# MICRO_MODULAR_batt2.net
KiCad netlist of a schematic drawn in EAGLE
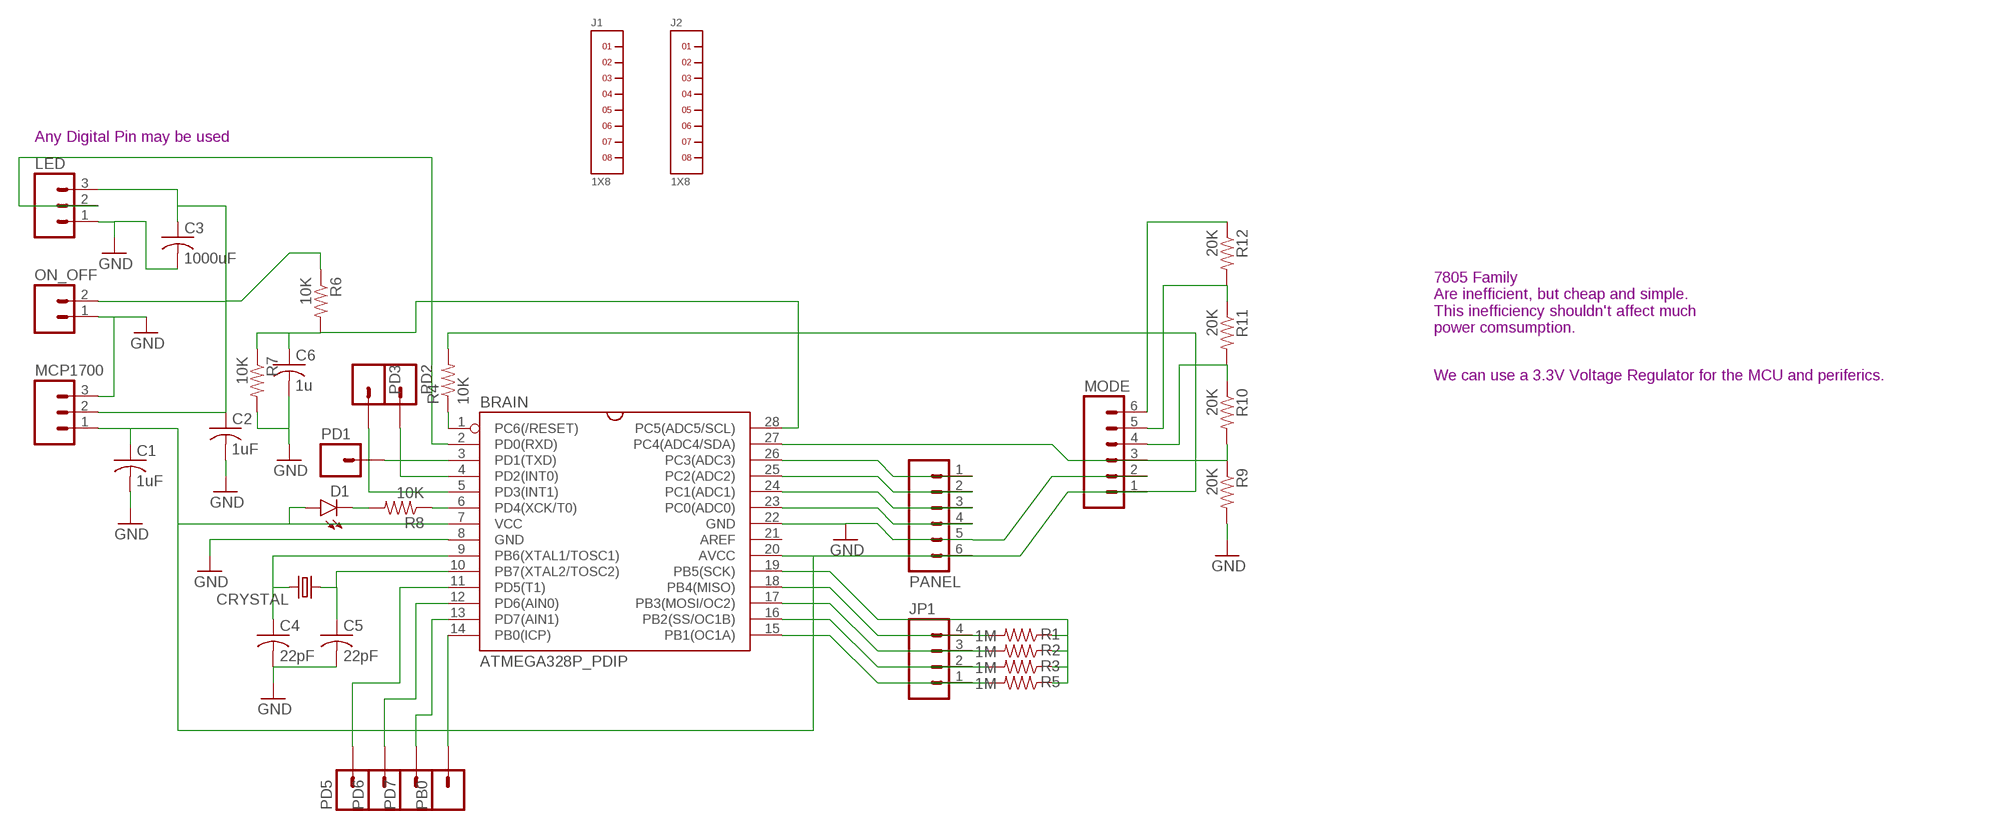
[diagram p0: schematic, sheet 1]

(export (version "E")
  (design (tool "Eeschema 10.0.6"))
  (components
    (comp (ref "BRAIN")
      (value "ATMEGA328P_PDIP")
      (footprint "eagle-import:DIL-28-3")
      (libsource (lib "eagle-import") (part "ATMEGA328P_PDIP"))
    )
    (comp (ref "C1")
      (value "1uF")
      (footprint "eagle-import:C050-025X075")
      (libsource (lib "eagle-import") (part "C-US050-025X075"))
    )
    (comp (ref "C2")
      (value "1uF")
      (footprint "eagle-import:C050-025X075")
      (libsource (lib "eagle-import") (part "C-US050-025X075"))
    )
    (comp (ref "C3")
      (value "1000uF")
      (footprint "eagle-import:C050-075X075")
      (libsource (lib "eagle-import") (part "C-US050-075X075"))
    )
    (comp (ref "C4")
      (value "22pF")
      (footprint "eagle-import:C025-024X044")
      (libsource (lib "eagle-import") (part "C-US025-024X044"))
    )
    (comp (ref "C5")
      (value "22pF")
      (footprint "eagle-import:C025-024X044")
      (libsource (lib "eagle-import") (part "C-US025-024X044"))
    )
    (comp (ref "C6")
      (value "1u")
      (footprint "eagle-import:C050-025X075")
      (libsource (lib "eagle-import") (part "C-US050-025X075"))
    )
    (comp (ref "CRYSTAL")
      (value "CRYSTALHC49US")
      (footprint "eagle-import:HC49US")
      (libsource (lib "eagle-import") (part "CRYSTALHC49US"))
    )
    (comp (ref "D1")
      (value "LED3MM")
      (footprint "eagle-import:LED3MM")
      (libsource (lib "eagle-import") (part "LED3MM"))
    )
    (comp (ref "J1")
      (value "1X8")
      (footprint "eagle-import:1X8")
      (libsource (lib "eagle-import") (part "1X8"))
    )
    (comp (ref "J2")
      (value "1X8")
      (footprint "eagle-import:1X8")
      (libsource (lib "eagle-import") (part "1X8"))
    )
    (comp (ref "JP1")
      (value "M04PTH")
      (footprint "eagle-import:1X04")
      (libsource (lib "eagle-import") (part "M04PTH"))
    )
    (comp (ref "LED")
      (value "M03PTH")
      (footprint "eagle-import:1X03")
      (libsource (lib "eagle-import") (part "M03PTH"))
    )
    (comp (ref "MCP1700")
      (value "M03PTH")
      (footprint "eagle-import:1X03")
      (libsource (lib "eagle-import") (part "M03PTH"))
    )
    (comp (ref "MODE")
      (value "M06SILK_FEMALE_PTH")
      (footprint "eagle-import:1X06")
      (libsource (lib "eagle-import") (part "M06SILK_FEMALE_PTH"))
    )
    (comp (ref "ON_OFF")
      (value "M02PTH")
      (footprint "eagle-import:1X02")
      (libsource (lib "eagle-import") (part "M02PTH"))
    )
    (comp (ref "PANEL")
      (value "M06NO_SILK_FEMALE_PTH")
      (footprint "eagle-import:1X06_NO_SILK")
      (libsource (lib "eagle-import") (part "M06NO_SILK_FEMALE_PTH"))
    )
    (comp (ref "PB0")
      (value "M01PTH")
      (footprint "eagle-import:1X01")
      (libsource (lib "eagle-import") (part "M01PTH"))
    )
    (comp (ref "PD1")
      (value "M01PTH")
      (footprint "eagle-import:1X01")
      (libsource (lib "eagle-import") (part "M01PTH"))
    )
    (comp (ref "PD2")
      (value "M01PTH")
      (footprint "eagle-import:1X01")
      (libsource (lib "eagle-import") (part "M01PTH"))
    )
    (comp (ref "PD3")
      (value "M01PTH")
      (footprint "eagle-import:1X01")
      (libsource (lib "eagle-import") (part "M01PTH"))
    )
    (comp (ref "PD5")
      (value "M01PTH")
      (footprint "eagle-import:1X01")
      (libsource (lib "eagle-import") (part "M01PTH"))
    )
    (comp (ref "PD6")
      (value "M01PTH")
      (footprint "eagle-import:1X01")
      (libsource (lib "eagle-import") (part "M01PTH"))
    )
    (comp (ref "PD7")
      (value "M01PTH")
      (footprint "eagle-import:1X01")
      (libsource (lib "eagle-import") (part "M01PTH"))
    )
    (comp (ref "R1")
      (value "1M")
      (footprint "eagle-import:AXIAL-0.3")
      (libsource (lib "eagle-import") (part "RESISTORAXIAL-0.3"))
    )
    (comp (ref "R2")
      (value "1M")
      (footprint "eagle-import:AXIAL-0.3")
      (libsource (lib "eagle-import") (part "RESISTORAXIAL-0.3"))
    )
    (comp (ref "R3")
      (value "1M")
      (footprint "eagle-import:AXIAL-0.3")
      (libsource (lib "eagle-import") (part "RESISTORAXIAL-0.3"))
    )
    (comp (ref "R4")
      (value "10K")
      (footprint "eagle-import:AXIAL-0.3")
      (libsource (lib "eagle-import") (part "RESISTORAXIAL-0.3"))
    )
    (comp (ref "R5")
      (value "1M")
      (footprint "eagle-import:AXIAL-0.3")
      (libsource (lib "eagle-import") (part "RESISTORAXIAL-0.3"))
    )
    (comp (ref "R6")
      (value "10K")
      (footprint "eagle-import:AXIAL-0.3")
      (libsource (lib "eagle-import") (part "RESISTORAXIAL-0.3"))
    )
    (comp (ref "R7")
      (value "10K")
      (footprint "eagle-import:AXIAL-0.3")
      (libsource (lib "eagle-import") (part "RESISTORAXIAL-0.3"))
    )
    (comp (ref "R8")
      (value "10K")
      (footprint "eagle-import:AXIAL-0.3")
      (libsource (lib "eagle-import") (part "RESISTORAXIAL-0.3"))
    )
    (comp (ref "R9")
      (value "20K")
      (footprint "eagle-import:AXIAL-0.3")
      (libsource (lib "eagle-import") (part "RESISTORAXIAL-0.3"))
    )
    (comp (ref "R10")
      (value "20K")
      (footprint "eagle-import:AXIAL-0.3")
      (libsource (lib "eagle-import") (part "RESISTORAXIAL-0.3"))
    )
    (comp (ref "R11")
      (value "20K")
      (footprint "eagle-import:AXIAL-0.3")
      (libsource (lib "eagle-import") (part "RESISTORAXIAL-0.3"))
    )
    (comp (ref "R12")
      (value "20K")
      (footprint "eagle-import:AXIAL-0.3")
      (libsource (lib "eagle-import") (part "RESISTORAXIAL-0.3"))
    )
  )
  (nets
    (net (code "1") (name "GND") (class "Default")
      (node (ref "BRAIN") (pin "22") (pinfunction "GND_22") (pintype "bidirectional"))
      (node (ref "BRAIN") (pin "8") (pinfunction "GND_8") (pintype "bidirectional"))
      (node (ref "C1") (pin "2") (pinfunction "2_2") (pintype "passive"))
      (node (ref "C2") (pin "2") (pinfunction "2_2") (pintype "passive"))
      (node (ref "C3") (pin "2") (pinfunction "2_2") (pintype "passive"))
      (node (ref "C4") (pin "2") (pinfunction "2_2") (pintype "passive"))
      (node (ref "C5") (pin "2") (pinfunction "2_2") (pintype "passive"))
      (node (ref "C6") (pin "2") (pinfunction "2_2") (pintype "passive"))
      (node (ref "LED") (pin "1") (pinfunction "1_1") (pintype "passive"))
      (node (ref "MCP1700") (pin "3") (pinfunction "3_3") (pintype "passive"))
      (node (ref "MODE") (pin "2") (pinfunction "2_2") (pintype "passive"))
      (node (ref "ON_OFF") (pin "1") (pinfunction "1_1") (pintype "passive"))
      (node (ref "PANEL") (pin "5") (pinfunction "5_5") (pintype "passive"))
      (node (ref "R7") (pin "P$2") (pinfunction "2_P$2") (pintype "passive"))
      (node (ref "R9") (pin "P$2") (pinfunction "2_P$2") (pintype "passive"))
    )
    (net (code "2") (name "Net-(BRAIN-AVCC)") (class "Default")
      (node (ref "BRAIN") (pin "20") (pinfunction "AVCC_20") (pintype "bidirectional"))
      (node (ref "BRAIN") (pin "7") (pinfunction "VCC_7") (pintype "bidirectional"))
      (node (ref "C1") (pin "1") (pinfunction "1_1") (pintype "passive"))
      (node (ref "D1") (pin "A") (pinfunction "A_A") (pintype "passive"))
      (node (ref "MCP1700") (pin "1") (pinfunction "1_1") (pintype "passive"))
      (node (ref "MODE") (pin "1") (pinfunction "1_1") (pintype "passive"))
      (node (ref "PANEL") (pin "6") (pinfunction "6_6") (pintype "passive"))
      (node (ref "R4") (pin "P$2") (pinfunction "2_P$2") (pintype "passive"))
    )
    (net (code "3") (name "Net-(BRAIN-PB0(ICP))") (class "Default")
      (node (ref "BRAIN") (pin "14") (pinfunction "PB0(ICP)_14") (pintype "bidirectional"))
      (node (ref "PB0") (pin "1") (pinfunction "1_1") (pintype "passive"))
    )
    (net (code "4") (name "Net-(BRAIN-PB1(OC1A))") (class "Default")
      (node (ref "BRAIN") (pin "15") (pinfunction "PB1(OC1A)_15") (pintype "bidirectional"))
      (node (ref "JP1") (pin "1") (pinfunction "1_1") (pintype "passive"))
      (node (ref "R5") (pin "P$2") (pinfunction "2_P$2") (pintype "passive"))
    )
    (net (code "5") (name "Net-(BRAIN-PB2(SS{slash}OC1B))") (class "Default")
      (node (ref "BRAIN") (pin "16") (pinfunction "PB2(SS/OC1B)_16") (pintype "bidirectional"))
      (node (ref "JP1") (pin "2") (pinfunction "2_2") (pintype "passive"))
      (node (ref "R3") (pin "P$2") (pinfunction "2_P$2") (pintype "passive"))
    )
    (net (code "6") (name "Net-(BRAIN-PB3(MOSI{slash}OC2))") (class "Default")
      (node (ref "BRAIN") (pin "17") (pinfunction "PB3(MOSI/OC2)_17") (pintype "bidirectional"))
      (node (ref "JP1") (pin "3") (pinfunction "3_3") (pintype "passive"))
      (node (ref "R2") (pin "P$2") (pinfunction "2_P$2") (pintype "passive"))
    )
    (net (code "7") (name "Net-(BRAIN-PB4(MISO))") (class "Default")
      (node (ref "BRAIN") (pin "18") (pinfunction "PB4(MISO)_18") (pintype "bidirectional"))
      (node (ref "JP1") (pin "4") (pinfunction "4_4") (pintype "passive"))
      (node (ref "R1") (pin "P$2") (pinfunction "2_P$2") (pintype "passive"))
    )
    (net (code "8") (name "Net-(BRAIN-PB5(SCK))") (class "Default")
      (node (ref "BRAIN") (pin "19") (pinfunction "PB5(SCK)_19") (pintype "bidirectional"))
      (node (ref "R1") (pin "P$1") (pinfunction "1_P$1") (pintype "passive"))
      (node (ref "R2") (pin "P$1") (pinfunction "1_P$1") (pintype "passive"))
      (node (ref "R3") (pin "P$1") (pinfunction "1_P$1") (pintype "passive"))
      (node (ref "R5") (pin "P$1") (pinfunction "1_P$1") (pintype "passive"))
    )
    (net (code "9") (name "Net-(BRAIN-PB6(XTAL1{slash}TOSC1))") (class "Default")
      (node (ref "BRAIN") (pin "9") (pinfunction "PB6(XTAL1/TOSC1)_9") (pintype "bidirectional"))
      (node (ref "C4") (pin "1") (pinfunction "1_1") (pintype "passive"))
      (node (ref "CRYSTAL") (pin "2") (pinfunction "2_2") (pintype "passive"))
    )
    (net (code "10") (name "Net-(BRAIN-PB7(XTAL2{slash}TOSC2))") (class "Default")
      (node (ref "BRAIN") (pin "10") (pinfunction "PB7(XTAL2/TOSC2)_10") (pintype "bidirectional"))
      (node (ref "C5") (pin "1") (pinfunction "1_1") (pintype "passive"))
      (node (ref "CRYSTAL") (pin "1") (pinfunction "1_1") (pintype "passive"))
    )
    (net (code "11") (name "Net-(BRAIN-PC0(ADC0))") (class "Default")
      (node (ref "BRAIN") (pin "23") (pinfunction "PC0(ADC0)_23") (pintype "bidirectional"))
      (node (ref "PANEL") (pin "4") (pinfunction "4_4") (pintype "passive"))
    )
    (net (code "12") (name "Net-(BRAIN-PC1(ADC1))") (class "Default")
      (node (ref "BRAIN") (pin "24") (pinfunction "PC1(ADC1)_24") (pintype "bidirectional"))
      (node (ref "PANEL") (pin "3") (pinfunction "3_3") (pintype "passive"))
    )
    (net (code "13") (name "Net-(BRAIN-PC2(ADC2))") (class "Default")
      (node (ref "BRAIN") (pin "25") (pinfunction "PC2(ADC2)_25") (pintype "bidirectional"))
      (node (ref "PANEL") (pin "2") (pinfunction "2_2") (pintype "passive"))
    )
    (net (code "14") (name "Net-(BRAIN-PC3(ADC3))") (class "Default")
      (node (ref "BRAIN") (pin "26") (pinfunction "PC3(ADC3)_26") (pintype "bidirectional"))
      (node (ref "PANEL") (pin "1") (pinfunction "1_1") (pintype "passive"))
    )
    (net (code "15") (name "Net-(BRAIN-PC4(ADC4{slash}SDA))") (class "Default")
      (node (ref "BRAIN") (pin "27") (pinfunction "PC4(ADC4/SDA)_27") (pintype "bidirectional"))
      (node (ref "MODE") (pin "3") (pinfunction "3_3") (pintype "passive"))
      (node (ref "R10") (pin "P$2") (pinfunction "2_P$2") (pintype "passive"))
      (node (ref "R9") (pin "P$1") (pinfunction "1_P$1") (pintype "passive"))
    )
    (net (code "16") (name "Net-(BRAIN-PC5(ADC5{slash}SCL))") (class "Default")
      (node (ref "BRAIN") (pin "28") (pinfunction "PC5(ADC5/SCL)_28") (pintype "bidirectional"))
      (node (ref "C6") (pin "1") (pinfunction "1_1") (pintype "passive"))
      (node (ref "R6") (pin "P$2") (pinfunction "2_P$2") (pintype "passive"))
      (node (ref "R7") (pin "P$1") (pinfunction "1_P$1") (pintype "passive"))
    )
    (net (code "17") (name "Net-(BRAIN-PC6({slash}RESET))") (class "Default")
      (node (ref "BRAIN") (pin "1") (pinfunction "PC6(/RESET)_1") (pintype "bidirectional"))
      (node (ref "R4") (pin "P$1") (pinfunction "1_P$1") (pintype "passive"))
    )
    (net (code "18") (name "Net-(BRAIN-PD0(RXD))") (class "Default")
      (node (ref "BRAIN") (pin "2") (pinfunction "PD0(RXD)_2") (pintype "bidirectional"))
      (node (ref "LED") (pin "2") (pinfunction "2_2") (pintype "passive"))
    )
    (net (code "19") (name "Net-(BRAIN-PD1(TXD))") (class "Default")
      (node (ref "BRAIN") (pin "3") (pinfunction "PD1(TXD)_3") (pintype "bidirectional"))
      (node (ref "PD1") (pin "1") (pinfunction "1_1") (pintype "passive"))
    )
    (net (code "20") (name "Net-(BRAIN-PD2(INT0))") (class "Default")
      (node (ref "BRAIN") (pin "4") (pinfunction "PD2(INT0)_4") (pintype "bidirectional"))
      (node (ref "PD2") (pin "1") (pinfunction "1_1") (pintype "passive"))
    )
    (net (code "21") (name "Net-(BRAIN-PD3(INT1))") (class "Default")
      (node (ref "BRAIN") (pin "5") (pinfunction "PD3(INT1)_5") (pintype "bidirectional"))
      (node (ref "PD3") (pin "1") (pinfunction "1_1") (pintype "passive"))
    )
    (net (code "22") (name "Net-(BRAIN-PD4(XCK{slash}T0))") (class "Default")
      (node (ref "BRAIN") (pin "6") (pinfunction "PD4(XCK/T0)_6") (pintype "bidirectional"))
      (node (ref "R8") (pin "P$1") (pinfunction "1_P$1") (pintype "passive"))
    )
    (net (code "23") (name "Net-(BRAIN-PD5(T1))") (class "Default")
      (node (ref "BRAIN") (pin "11") (pinfunction "PD5(T1)_11") (pintype "bidirectional"))
      (node (ref "PD5") (pin "1") (pinfunction "1_1") (pintype "passive"))
    )
    (net (code "24") (name "Net-(BRAIN-PD6(AIN0))") (class "Default")
      (node (ref "BRAIN") (pin "12") (pinfunction "PD6(AIN0)_12") (pintype "bidirectional"))
      (node (ref "PD6") (pin "1") (pinfunction "1_1") (pintype "passive"))
    )
    (net (code "25") (name "Net-(BRAIN-PD7(AIN1))") (class "Default")
      (node (ref "BRAIN") (pin "13") (pinfunction "PD7(AIN1)_13") (pintype "bidirectional"))
      (node (ref "PD7") (pin "1") (pinfunction "1_1") (pintype "passive"))
    )
    (net (code "26") (name "Net-(D1-C)") (class "Default")
      (node (ref "D1") (pin "K") (pinfunction "C_K") (pintype "passive"))
      (node (ref "R8") (pin "P$2") (pinfunction "2_P$2") (pintype "passive"))
    )
    (net (code "27") (name "Net-(R6-1)") (class "Default")
      (node (ref "C2") (pin "1") (pinfunction "1_1") (pintype "passive"))
      (node (ref "C3") (pin "1") (pinfunction "1_1") (pintype "passive"))
      (node (ref "LED") (pin "3") (pinfunction "3_3") (pintype "passive"))
      (node (ref "MCP1700") (pin "2") (pinfunction "2_2") (pintype "passive"))
      (node (ref "ON_OFF") (pin "2") (pinfunction "2_2") (pintype "passive"))
      (node (ref "R6") (pin "P$1") (pinfunction "1_P$1") (pintype "passive"))
    )
    (net (code "28") (name "Net-(R10-1)") (class "Default")
      (node (ref "MODE") (pin "4") (pinfunction "4_4") (pintype "passive"))
      (node (ref "R10") (pin "P$1") (pinfunction "1_P$1") (pintype "passive"))
      (node (ref "R11") (pin "P$2") (pinfunction "2_P$2") (pintype "passive"))
    )
    (net (code "29") (name "Net-(R11-1)") (class "Default")
      (node (ref "MODE") (pin "5") (pinfunction "5_5") (pintype "passive"))
      (node (ref "R11") (pin "P$1") (pinfunction "1_P$1") (pintype "passive"))
      (node (ref "R12") (pin "P$2") (pinfunction "2_P$2") (pintype "passive"))
    )
    (net (code "30") (name "Net-(R12-1)") (class "Default")
      (node (ref "MODE") (pin "6") (pinfunction "6_6") (pintype "passive"))
      (node (ref "R12") (pin "P$1") (pinfunction "1_P$1") (pintype "passive"))
    )
    (net (code "31") (name "unconnected-(BRAIN-AREF-Pad21)") (class "Default")
      (node (ref "BRAIN") (pin "21") (pinfunction "AREF_21") (pintype "bidirectional"))
    )
    (net (code "32") (name "unconnected-(J1-Pad1)") (class "Default")
      (node (ref "J1") (pin "1") (pinfunction "1_1") (pintype "bidirectional"))
    )
    (net (code "33") (name "unconnected-(J1-Pad2)") (class "Default")
      (node (ref "J1") (pin "2") (pinfunction "2_2") (pintype "bidirectional"))
    )
    (net (code "34") (name "unconnected-(J1-Pad3)") (class "Default")
      (node (ref "J1") (pin "3") (pinfunction "3_3") (pintype "bidirectional"))
    )
    (net (code "35") (name "unconnected-(J1-Pad4)") (class "Default")
      (node (ref "J1") (pin "4") (pinfunction "4_4") (pintype "bidirectional"))
    )
    (net (code "36") (name "unconnected-(J1-Pad5)") (class "Default")
      (node (ref "J1") (pin "5") (pinfunction "5_5") (pintype "bidirectional"))
    )
    (net (code "37") (name "unconnected-(J1-Pad6)") (class "Default")
      (node (ref "J1") (pin "6") (pinfunction "6_6") (pintype "bidirectional"))
    )
    (net (code "38") (name "unconnected-(J1-Pad7)") (class "Default")
      (node (ref "J1") (pin "7") (pinfunction "7_7") (pintype "bidirectional"))
    )
    (net (code "39") (name "unconnected-(J1-Pad8)") (class "Default")
      (node (ref "J1") (pin "8") (pinfunction "8_8") (pintype "bidirectional"))
    )
    (net (code "40") (name "unconnected-(J2-Pad1)") (class "Default")
      (node (ref "J2") (pin "1") (pinfunction "1_1") (pintype "bidirectional"))
    )
    (net (code "41") (name "unconnected-(J2-Pad2)") (class "Default")
      (node (ref "J2") (pin "2") (pinfunction "2_2") (pintype "bidirectional"))
    )
    (net (code "42") (name "unconnected-(J2-Pad3)") (class "Default")
      (node (ref "J2") (pin "3") (pinfunction "3_3") (pintype "bidirectional"))
    )
    (net (code "43") (name "unconnected-(J2-Pad4)") (class "Default")
      (node (ref "J2") (pin "4") (pinfunction "4_4") (pintype "bidirectional"))
    )
    (net (code "44") (name "unconnected-(J2-Pad5)") (class "Default")
      (node (ref "J2") (pin "5") (pinfunction "5_5") (pintype "bidirectional"))
    )
    (net (code "45") (name "unconnected-(J2-Pad6)") (class "Default")
      (node (ref "J2") (pin "6") (pinfunction "6_6") (pintype "bidirectional"))
    )
    (net (code "46") (name "unconnected-(J2-Pad7)") (class "Default")
      (node (ref "J2") (pin "7") (pinfunction "7_7") (pintype "bidirectional"))
    )
    (net (code "47") (name "unconnected-(J2-Pad8)") (class "Default")
      (node (ref "J2") (pin "8") (pinfunction "8_8") (pintype "bidirectional"))
    )
  )
)
